# platform_smd2_map.net
KiCad netlist of a schematic drawn in EAGLE
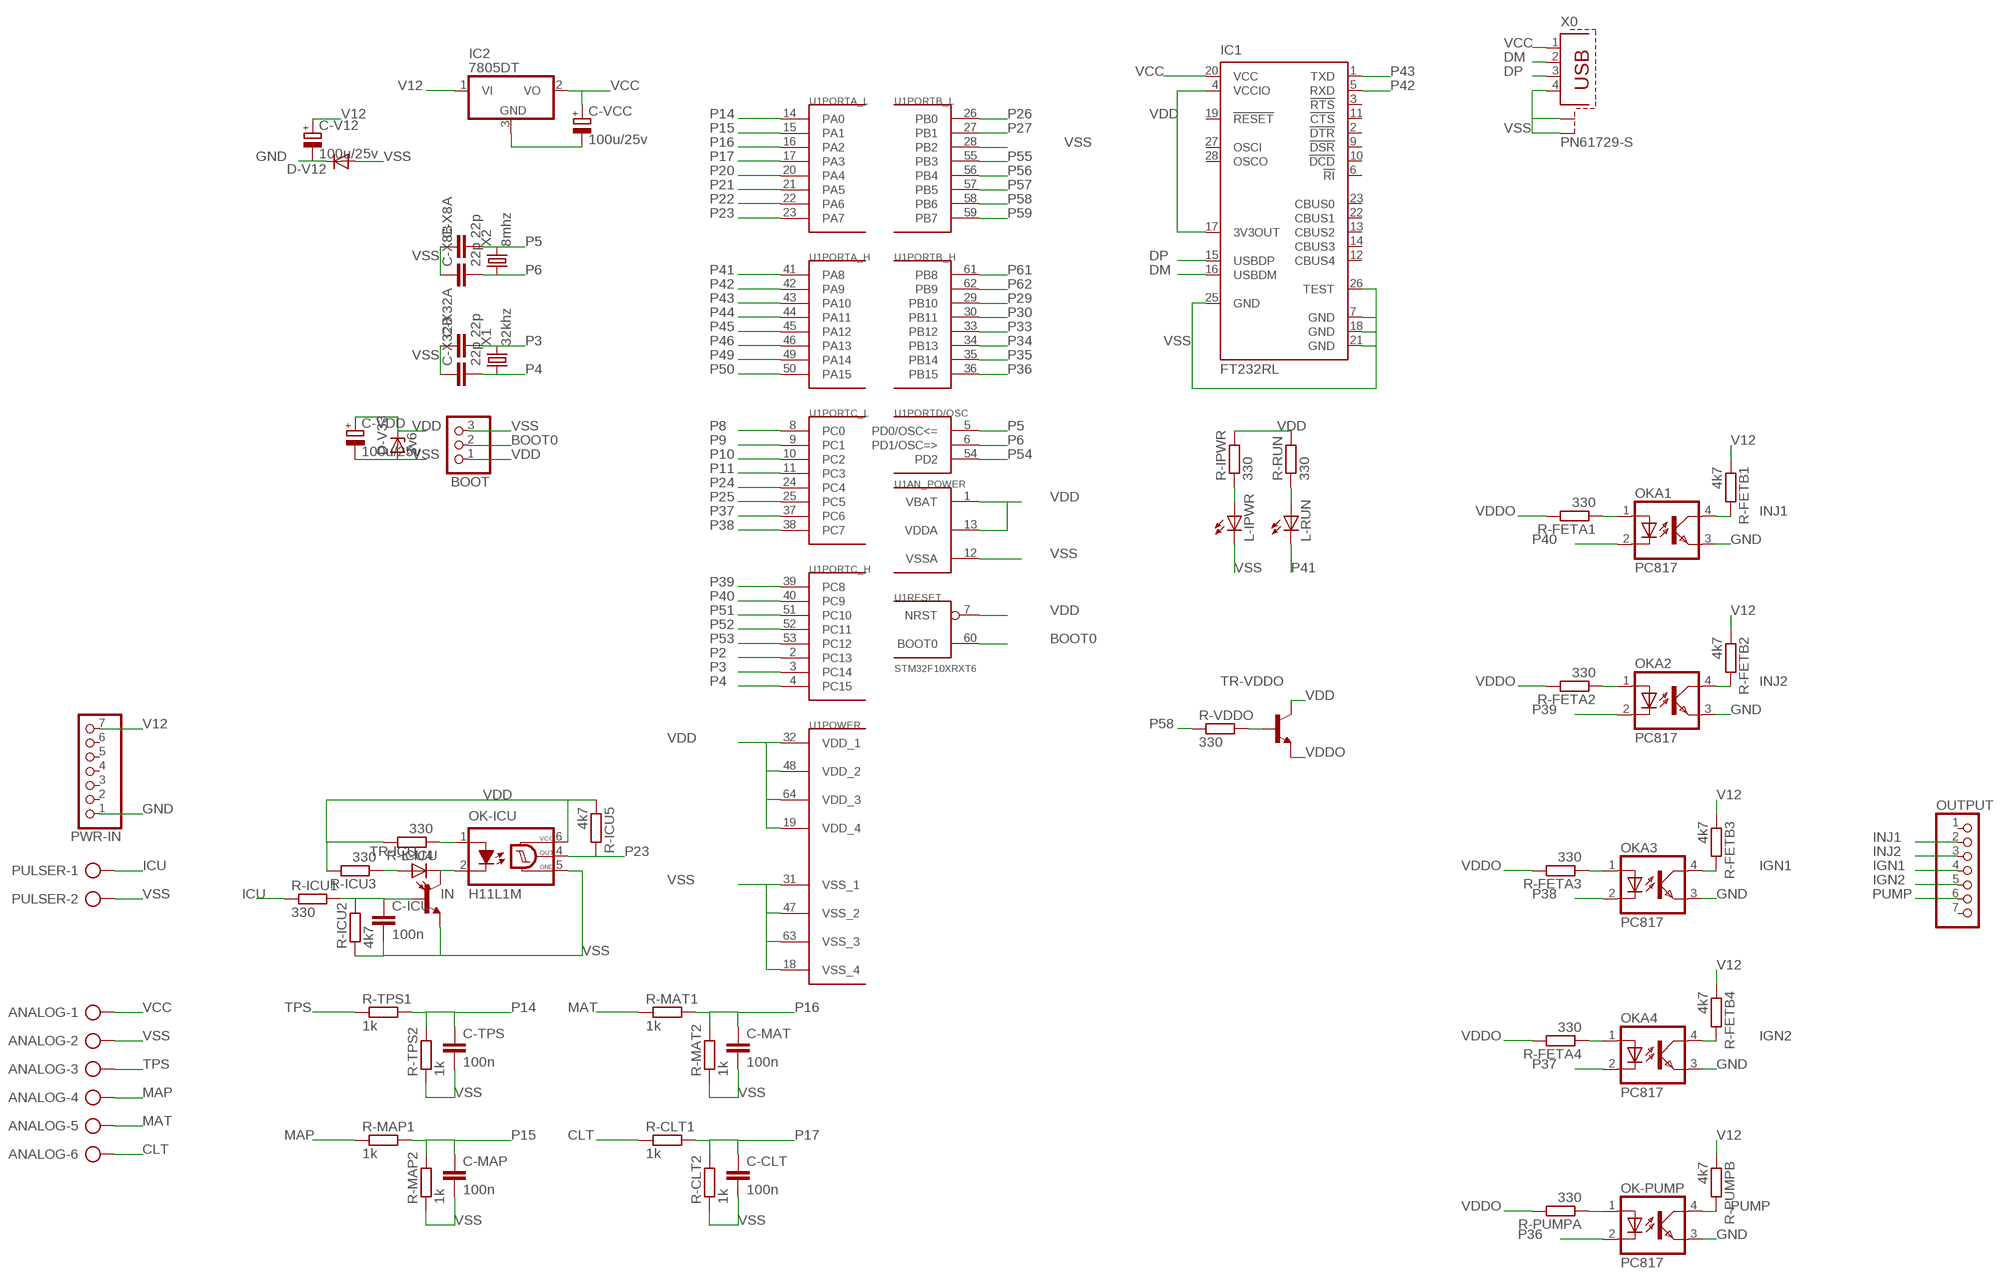
[diagram p0: schematic, sheet 1]

(export (version "E")
  (design (tool "Eeschema 10.0.6"))
  (components
    (comp (ref "ANALOG")
      (value "AK300/6")
      (footprint "eagle-import:AK300_6")
      (libsource (lib "eagle-import") (part "AK300/6"))
    )
    (comp (ref "BOOT")
      (value "PINHD-1X3")
      (footprint "eagle-import:1X03")
      (libsource (lib "eagle-import") (part "PINHD-1X3"))
    )
    (comp (ref "C-CLT")
      (value "100n")
      (footprint "eagle-import:C1206")
      (libsource (lib "eagle-import") (part "C-EUC1206"))
    )
    (comp (ref "C-ICU")
      (value "100n")
      (footprint "eagle-import:C1206")
      (libsource (lib "eagle-import") (part "C-EUC1206"))
    )
    (comp (ref "C-MAP")
      (value "100n")
      (footprint "eagle-import:C1206")
      (libsource (lib "eagle-import") (part "C-EUC1206"))
    )
    (comp (ref "C-MAT")
      (value "100n")
      (footprint "eagle-import:C1206")
      (libsource (lib "eagle-import") (part "C-EUC1206"))
    )
    (comp (ref "C-TPS")
      (value "100n")
      (footprint "eagle-import:C1206")
      (libsource (lib "eagle-import") (part "C-EUC1206"))
    )
    (comp (ref "C-V12")
      (value "100u/25v")
      (footprint "eagle-import:PANASONIC_D")
      (libsource (lib "eagle-import") (part "CPOL-EUD"))
    )
    (comp (ref "C-VCC")
      (value "100u/25v")
      (footprint "eagle-import:PANASONIC_D")
      (libsource (lib "eagle-import") (part "CPOL-EUD"))
    )
    (comp (ref "C-VDD")
      (value "100u/25v")
      (footprint "eagle-import:PANASONIC_D")
      (libsource (lib "eagle-import") (part "CPOL-EUD"))
    )
    (comp (ref "C-X8A")
      (value "22p")
      (footprint "eagle-import:C1206")
      (libsource (lib "eagle-import") (part "C-EUC1206"))
    )
    (comp (ref "C-X8B")
      (value "22p")
      (footprint "eagle-import:C1206")
      (libsource (lib "eagle-import") (part "C-EUC1206"))
    )
    (comp (ref "C-X32A")
      (value "22p")
      (footprint "eagle-import:C1206")
      (libsource (lib "eagle-import") (part "C-EUC1206"))
    )
    (comp (ref "C-X32B")
      (value "22p")
      (footprint "eagle-import:C1206")
      (libsource (lib "eagle-import") (part "C-EUC1206"))
    )
    (comp (ref "D-V12")
      (value "DIODE-SMB")
      (footprint "eagle-import:SMB")
      (libsource (lib "eagle-import") (part "DIODE-SMB"))
    )
    (comp (ref "D-V33")
      (value "3v6")
      (footprint "eagle-import:SMB")
      (libsource (lib "eagle-import") (part "ZENER-DIODESMB"))
    )
    (comp (ref "IC1")
      (value "FT232RL")
      (footprint "eagle-import:SSOP28")
      (libsource (lib "eagle-import") (part "FT232RL"))
    )
    (comp (ref "IC2")
      (value "7805DT")
      (footprint "eagle-import:TO252")
      (libsource (lib "eagle-import") (part "78DT05"))
    )
    (comp (ref "L-ICU")
      (value "LEDSML0805")
      (footprint "eagle-import:SML0805")
      (libsource (lib "eagle-import") (part "LEDSML0805"))
    )
    (comp (ref "L-IPWR")
      (value "LEDSMT1206")
      (footprint "eagle-import:1206")
      (libsource (lib "eagle-import") (part "LEDSMT1206"))
    )
    (comp (ref "L-RUN")
      (value "LEDSMT1206")
      (footprint "eagle-import:1206")
      (libsource (lib "eagle-import") (part "LEDSMT1206"))
    )
    (comp (ref "OK-ICU")
      (value "H11L1M")
      (footprint "eagle-import:DIL06")
      (fields (field (name "MF") "FAIRCHILD SEMICONDUCTOR") (field (name "MPN") "H11L1-M"))
      (libsource (lib "eagle-import") (part "H11LM1"))
    )
    (comp (ref "OK-PUMP")
      (value "PC817")
      (footprint "eagle-import:DIL04")
      (fields (field (name "MPN") "PC817X4J000F"))
      (libsource (lib "eagle-import") (part "PC817"))
    )
    (comp (ref "OKA1")
      (value "PC817")
      (footprint "eagle-import:DIL04")
      (fields (field (name "MPN") "PC817X4J000F"))
      (libsource (lib "eagle-import") (part "PC817"))
    )
    (comp (ref "OKA2")
      (value "PC817")
      (footprint "eagle-import:DIL04")
      (fields (field (name "MPN") "PC817X4J000F"))
      (libsource (lib "eagle-import") (part "PC817"))
    )
    (comp (ref "OKA3")
      (value "PC817")
      (footprint "eagle-import:DIL04")
      (fields (field (name "MPN") "PC817X4J000F"))
      (libsource (lib "eagle-import") (part "PC817"))
    )
    (comp (ref "OKA4")
      (value "PC817")
      (footprint "eagle-import:DIL04")
      (fields (field (name "MPN") "PC817X4J000F"))
      (libsource (lib "eagle-import") (part "PC817"))
    )
    (comp (ref "OUTPUT")
      (value "PINHD-1X7")
      (footprint "eagle-import:1X07")
      (libsource (lib "eagle-import") (part "PINHD-1X7"))
    )
    (comp (ref "PULSER")
      (value "AK300/2")
      (footprint "eagle-import:AK300_2")
      (libsource (lib "eagle-import") (part "AK300/2"))
    )
    (comp (ref "PWR-IN")
      (value "PINHD-1X7")
      (footprint "eagle-import:1X07")
      (libsource (lib "eagle-import") (part "PINHD-1X7"))
    )
    (comp (ref "R-CLT1")
      (value "1k")
      (footprint "eagle-import:R1206")
      (libsource (lib "eagle-import") (part "R-EU_R1206"))
    )
    (comp (ref "R-CLT2")
      (value "1k")
      (footprint "eagle-import:R1206")
      (libsource (lib "eagle-import") (part "R-EU_R1206"))
    )
    (comp (ref "R-FETA1")
      (value "330")
      (footprint "eagle-import:R1206")
      (libsource (lib "eagle-import") (part "R-EU_R1206"))
    )
    (comp (ref "R-FETA2")
      (value "330")
      (footprint "eagle-import:R1206")
      (libsource (lib "eagle-import") (part "R-EU_R1206"))
    )
    (comp (ref "R-FETA3")
      (value "330")
      (footprint "eagle-import:R1206")
      (libsource (lib "eagle-import") (part "R-EU_R1206"))
    )
    (comp (ref "R-FETA4")
      (value "330")
      (footprint "eagle-import:R1206")
      (libsource (lib "eagle-import") (part "R-EU_R1206"))
    )
    (comp (ref "R-FETB1")
      (value "4k7")
      (footprint "eagle-import:R1206")
      (libsource (lib "eagle-import") (part "R-EU_R1206"))
    )
    (comp (ref "R-FETB2")
      (value "4k7")
      (footprint "eagle-import:R1206")
      (libsource (lib "eagle-import") (part "R-EU_R1206"))
    )
    (comp (ref "R-FETB3")
      (value "4k7")
      (footprint "eagle-import:R1206")
      (libsource (lib "eagle-import") (part "R-EU_R1206"))
    )
    (comp (ref "R-FETB4")
      (value "4k7")
      (footprint "eagle-import:R1206")
      (libsource (lib "eagle-import") (part "R-EU_R1206"))
    )
    (comp (ref "R-ICU1")
      (value "330")
      (footprint "eagle-import:R1206")
      (libsource (lib "eagle-import") (part "R-EU_R1206"))
    )
    (comp (ref "R-ICU2")
      (value "4k7")
      (footprint "eagle-import:R1206")
      (libsource (lib "eagle-import") (part "R-EU_R1206"))
    )
    (comp (ref "R-ICU3")
      (value "330")
      (footprint "eagle-import:R1206")
      (libsource (lib "eagle-import") (part "R-EU_R1206"))
    )
    (comp (ref "R-ICU4")
      (value "330")
      (footprint "eagle-import:R1206")
      (libsource (lib "eagle-import") (part "R-EU_R1206"))
    )
    (comp (ref "R-ICU5")
      (value "4k7")
      (footprint "eagle-import:R1206")
      (libsource (lib "eagle-import") (part "R-EU_R1206"))
    )
    (comp (ref "R-IPWR")
      (value "330")
      (footprint "eagle-import:R1206")
      (libsource (lib "eagle-import") (part "R-EU_R1206"))
    )
    (comp (ref "R-MAP1")
      (value "1k")
      (footprint "eagle-import:R1206")
      (libsource (lib "eagle-import") (part "R-EU_R1206"))
    )
    (comp (ref "R-MAP2")
      (value "1k")
      (footprint "eagle-import:R1206")
      (libsource (lib "eagle-import") (part "R-EU_R1206"))
    )
    (comp (ref "R-MAT1")
      (value "1k")
      (footprint "eagle-import:R1206")
      (libsource (lib "eagle-import") (part "R-EU_R1206"))
    )
    (comp (ref "R-MAT2")
      (value "1k")
      (footprint "eagle-import:R1206")
      (libsource (lib "eagle-import") (part "R-EU_R1206"))
    )
    (comp (ref "R-PUMPA")
      (value "330")
      (footprint "eagle-import:R1206")
      (libsource (lib "eagle-import") (part "R-EU_R1206"))
    )
    (comp (ref "R-PUMPB")
      (value "4k7")
      (footprint "eagle-import:R1206")
      (libsource (lib "eagle-import") (part "R-EU_R1206"))
    )
    (comp (ref "R-RUN")
      (value "330")
      (footprint "eagle-import:R1206")
      (libsource (lib "eagle-import") (part "R-EU_R1206"))
    )
    (comp (ref "R-TPS1")
      (value "1k")
      (footprint "eagle-import:R1206")
      (libsource (lib "eagle-import") (part "R-EU_R1206"))
    )
    (comp (ref "R-TPS2")
      (value "1k")
      (footprint "eagle-import:R1206")
      (libsource (lib "eagle-import") (part "R-EU_R1206"))
    )
    (comp (ref "R-VDDO")
      (value "330")
      (footprint "eagle-import:R0805")
      (libsource (lib "eagle-import") (part "R-EU_R0805"))
    )
    (comp (ref "TR-ICU")
      (value "MMBT3904LT1-NPN-SOT23-BEC")
      (footprint "eagle-import:SOT23-BEC")
      (libsource (lib "eagle-import") (part "-NPN-SOT23-BECMMBT3904LT1"))
    )
    (comp (ref "TR-VDDO")
      (value "MMBT3904LT1-NPN-SOT23-BEC")
      (footprint "eagle-import:SOT23-BEC")
      (libsource (lib "eagle-import") (part "-NPN-SOT23-BECMMBT3904LT1"))
    )
    (comp (ref "U1")
      (value "STM32F10XRXT6")
      (footprint "eagle-import:TQFP64")
      (libsource (lib "eagle-import") (part "STM32F10XRXT6"))
    )
    (comp (ref "X0")
      (value "PN61729-S")
      (footprint "eagle-import:PN61729-S")
      (libsource (lib "eagle-import") (part "PN61729-S"))
    )
    (comp (ref "X1")
      (value "32khz")
      (footprint "eagle-import:TC26V")
      (libsource (lib "eagle-import") (part "CRYSTALTC26V"))
    )
    (comp (ref "X2")
      (value "8mhz")
      (footprint "eagle-import:HC49U-V")
      (libsource (lib "eagle-import") (part "CRYSTALHC49U-V"))
    )
  )
  (nets
    (net (code "1") (name "/BOOT0") (class "Default")
      (node (ref "BOOT") (pin "2") (pinfunction "2_2") (pintype "passive"))
      (node (ref "U1") (pin "60") (pinfunction "BOOT0_60") (pintype "input"))
    )
    (net (code "2") (name "/CLT") (class "Default")
      (node (ref "ANALOG") (pin "6") (pinfunction "KL_6") (pintype "passive"))
      (node (ref "R-CLT1") (pin "1") (pinfunction "1_1") (pintype "passive"))
    )
    (net (code "3") (name "/DM") (class "Default")
      (node (ref "IC1") (pin "16") (pinfunction "USBDM_16") (pintype "bidirectional"))
      (node (ref "X0") (pin "2") (pinfunction "2_2") (pintype "passive"))
    )
    (net (code "4") (name "/DP") (class "Default")
      (node (ref "IC1") (pin "15") (pinfunction "USBDP_15") (pintype "bidirectional"))
      (node (ref "X0") (pin "3") (pinfunction "3_3") (pintype "passive"))
    )
    (net (code "5") (name "/GND") (class "Default")
      (node (ref "C-V12") (pin "-") (pinfunction "-_-") (pintype "passive"))
      (node (ref "D-V12") (pin "C") (pinfunction "C_C") (pintype "passive"))
      (node (ref "OK-PUMP") (pin "3") (pinfunction "EMIT_3") (pintype "passive"))
      (node (ref "OKA1") (pin "3") (pinfunction "EMIT_3") (pintype "passive"))
      (node (ref "OKA2") (pin "3") (pinfunction "EMIT_3") (pintype "passive"))
      (node (ref "OKA3") (pin "3") (pinfunction "EMIT_3") (pintype "passive"))
      (node (ref "OKA4") (pin "3") (pinfunction "EMIT_3") (pintype "passive"))
      (node (ref "PWR-IN") (pin "1") (pinfunction "1_1") (pintype "passive"))
    )
    (net (code "6") (name "/ICU") (class "Default")
      (node (ref "PULSER") (pin "1") (pinfunction "KL_1") (pintype "passive"))
      (node (ref "R-ICU1") (pin "1") (pinfunction "1_1") (pintype "passive"))
    )
    (net (code "7") (name "/IGN1") (class "Default")
      (node (ref "OKA3") (pin "4") (pinfunction "COL_4") (pintype "passive"))
      (node (ref "OUTPUT") (pin "4") (pinfunction "4_4") (pintype "passive"))
      (node (ref "R-FETB3") (pin "2") (pinfunction "2_2") (pintype "passive"))
    )
    (net (code "8") (name "/IGN2") (class "Default")
      (node (ref "OKA4") (pin "4") (pinfunction "COL_4") (pintype "passive"))
      (node (ref "OUTPUT") (pin "5") (pinfunction "5_5") (pintype "passive"))
      (node (ref "R-FETB4") (pin "2") (pinfunction "2_2") (pintype "passive"))
    )
    (net (code "9") (name "/IN") (class "Default")
      (node (ref "L-ICU") (pin "C") (pinfunction "C_C") (pintype "passive"))
      (node (ref "OK-ICU") (pin "2") (pinfunction "C_2") (pintype "passive"))
      (node (ref "TR-ICU") (pin "C") (pinfunction "C_C") (pintype "passive"))
    )
    (net (code "10") (name "/INJ1") (class "Default")
      (node (ref "OKA1") (pin "4") (pinfunction "COL_4") (pintype "passive"))
      (node (ref "OUTPUT") (pin "2") (pinfunction "2_2") (pintype "passive"))
      (node (ref "R-FETB1") (pin "2") (pinfunction "2_2") (pintype "passive"))
    )
    (net (code "11") (name "/INJ2") (class "Default")
      (node (ref "OKA2") (pin "4") (pinfunction "COL_4") (pintype "passive"))
      (node (ref "OUTPUT") (pin "3") (pinfunction "3_3") (pintype "passive"))
      (node (ref "R-FETB2") (pin "2") (pinfunction "2_2") (pintype "passive"))
    )
    (net (code "12") (name "/MAP") (class "Default")
      (node (ref "ANALOG") (pin "4") (pinfunction "KL_4") (pintype "passive"))
      (node (ref "R-MAP1") (pin "1") (pinfunction "1_1") (pintype "passive"))
    )
    (net (code "13") (name "/MAT") (class "Default")
      (node (ref "ANALOG") (pin "5") (pinfunction "KL_5") (pintype "passive"))
      (node (ref "R-MAT1") (pin "1") (pinfunction "1_1") (pintype "passive"))
    )
    (net (code "14") (name "/P2") (class "Default")
      (node (ref "U1") (pin "2") (pinfunction "PC13_2") (pintype "bidirectional"))
    )
    (net (code "15") (name "/P3") (class "Default")
      (node (ref "C-X32A") (pin "2") (pinfunction "2_2") (pintype "passive"))
      (node (ref "U1") (pin "3") (pinfunction "PC14_3") (pintype "bidirectional"))
      (node (ref "X1") (pin "2") (pinfunction "2_2") (pintype "passive"))
    )
    (net (code "16") (name "/P4") (class "Default")
      (node (ref "C-X32B") (pin "2") (pinfunction "2_2") (pintype "passive"))
      (node (ref "U1") (pin "4") (pinfunction "PC15_4") (pintype "bidirectional"))
      (node (ref "X1") (pin "1") (pinfunction "1_1") (pintype "passive"))
    )
    (net (code "17") (name "/P5") (class "Default")
      (node (ref "C-X8A") (pin "2") (pinfunction "2_2") (pintype "passive"))
      (node (ref "U1") (pin "5") (pinfunction "PD0/OSC<=_5") (pintype "bidirectional"))
      (node (ref "X2") (pin "2") (pinfunction "2_2") (pintype "passive"))
    )
    (net (code "18") (name "/P6") (class "Default")
      (node (ref "C-X8B") (pin "2") (pinfunction "2_2") (pintype "passive"))
      (node (ref "U1") (pin "6") (pinfunction "PD1/OSC=>_6") (pintype "bidirectional"))
      (node (ref "X2") (pin "1") (pinfunction "1_1") (pintype "passive"))
    )
    (net (code "19") (name "/P8") (class "Default")
      (node (ref "U1") (pin "8") (pinfunction "PC0_8") (pintype "bidirectional"))
    )
    (net (code "20") (name "/P9") (class "Default")
      (node (ref "U1") (pin "9") (pinfunction "PC1_9") (pintype "bidirectional"))
    )
    (net (code "21") (name "/P10") (class "Default")
      (node (ref "U1") (pin "10") (pinfunction "PC2_10") (pintype "bidirectional"))
    )
    (net (code "22") (name "/P11") (class "Default")
      (node (ref "U1") (pin "11") (pinfunction "PC3_11") (pintype "bidirectional"))
    )
    (net (code "23") (name "/P14") (class "Default")
      (node (ref "C-TPS") (pin "1") (pinfunction "1_1") (pintype "passive"))
      (node (ref "R-TPS1") (pin "2") (pinfunction "2_2") (pintype "passive"))
      (node (ref "R-TPS2") (pin "2") (pinfunction "2_2") (pintype "passive"))
      (node (ref "U1") (pin "14") (pinfunction "PA0_14") (pintype "bidirectional"))
    )
    (net (code "24") (name "/P15") (class "Default")
      (node (ref "C-MAP") (pin "1") (pinfunction "1_1") (pintype "passive"))
      (node (ref "R-MAP1") (pin "2") (pinfunction "2_2") (pintype "passive"))
      (node (ref "R-MAP2") (pin "2") (pinfunction "2_2") (pintype "passive"))
      (node (ref "U1") (pin "15") (pinfunction "PA1_15") (pintype "bidirectional"))
    )
    (net (code "25") (name "/P16") (class "Default")
      (node (ref "C-MAT") (pin "1") (pinfunction "1_1") (pintype "passive"))
      (node (ref "R-MAT1") (pin "2") (pinfunction "2_2") (pintype "passive"))
      (node (ref "R-MAT2") (pin "2") (pinfunction "2_2") (pintype "passive"))
      (node (ref "U1") (pin "16") (pinfunction "PA2_16") (pintype "bidirectional"))
    )
    (net (code "26") (name "/P17") (class "Default")
      (node (ref "C-CLT") (pin "1") (pinfunction "1_1") (pintype "passive"))
      (node (ref "R-CLT1") (pin "2") (pinfunction "2_2") (pintype "passive"))
      (node (ref "R-CLT2") (pin "2") (pinfunction "2_2") (pintype "passive"))
      (node (ref "U1") (pin "17") (pinfunction "PA3_17") (pintype "bidirectional"))
    )
    (net (code "27") (name "/P20") (class "Default")
      (node (ref "U1") (pin "20") (pinfunction "PA4_20") (pintype "bidirectional"))
    )
    (net (code "28") (name "/P21") (class "Default")
      (node (ref "U1") (pin "21") (pinfunction "PA5_21") (pintype "bidirectional"))
    )
    (net (code "29") (name "/P22") (class "Default")
      (node (ref "U1") (pin "22") (pinfunction "PA6_22") (pintype "bidirectional"))
    )
    (net (code "30") (name "/P23") (class "Default")
      (node (ref "OK-ICU") (pin "4") (pinfunction "OUT_4") (pintype "output"))
      (node (ref "R-ICU5") (pin "2") (pinfunction "2_2") (pintype "passive"))
      (node (ref "U1") (pin "23") (pinfunction "PA7_23") (pintype "bidirectional"))
    )
    (net (code "31") (name "/P24") (class "Default")
      (node (ref "U1") (pin "24") (pinfunction "PC4_24") (pintype "bidirectional"))
    )
    (net (code "32") (name "/P25") (class "Default")
      (node (ref "U1") (pin "25") (pinfunction "PC5_25") (pintype "bidirectional"))
    )
    (net (code "33") (name "/P26") (class "Default")
      (node (ref "U1") (pin "26") (pinfunction "PB0_26") (pintype "bidirectional"))
    )
    (net (code "34") (name "/P27") (class "Default")
      (node (ref "U1") (pin "27") (pinfunction "PB1_27") (pintype "bidirectional"))
    )
    (net (code "35") (name "/P29") (class "Default")
      (node (ref "U1") (pin "29") (pinfunction "PB10_29") (pintype "bidirectional"))
    )
    (net (code "36") (name "/P30") (class "Default")
      (node (ref "U1") (pin "30") (pinfunction "PB11_30") (pintype "bidirectional"))
    )
    (net (code "37") (name "/P33") (class "Default")
      (node (ref "U1") (pin "33") (pinfunction "PB12_33") (pintype "bidirectional"))
    )
    (net (code "38") (name "/P34") (class "Default")
      (node (ref "U1") (pin "34") (pinfunction "PB13_34") (pintype "bidirectional"))
    )
    (net (code "39") (name "/P35") (class "Default")
      (node (ref "U1") (pin "35") (pinfunction "PB14_35") (pintype "bidirectional"))
    )
    (net (code "40") (name "/P36") (class "Default")
      (node (ref "OK-PUMP") (pin "2") (pinfunction "C_2") (pintype "passive"))
      (node (ref "U1") (pin "36") (pinfunction "PB15_36") (pintype "bidirectional"))
    )
    (net (code "41") (name "/P37") (class "Default")
      (node (ref "OKA4") (pin "2") (pinfunction "C_2") (pintype "passive"))
      (node (ref "U1") (pin "37") (pinfunction "PC6_37") (pintype "bidirectional"))
    )
    (net (code "42") (name "/P38") (class "Default")
      (node (ref "OKA3") (pin "2") (pinfunction "C_2") (pintype "passive"))
      (node (ref "U1") (pin "38") (pinfunction "PC7_38") (pintype "bidirectional"))
    )
    (net (code "43") (name "/P39") (class "Default")
      (node (ref "OKA2") (pin "2") (pinfunction "C_2") (pintype "passive"))
      (node (ref "U1") (pin "39") (pinfunction "PC8_39") (pintype "bidirectional"))
    )
    (net (code "44") (name "/P40") (class "Default")
      (node (ref "OKA1") (pin "2") (pinfunction "C_2") (pintype "passive"))
      (node (ref "U1") (pin "40") (pinfunction "PC9_40") (pintype "bidirectional"))
    )
    (net (code "45") (name "/P41") (class "Default")
      (node (ref "L-RUN") (pin "C") (pinfunction "C_C") (pintype "passive"))
      (node (ref "U1") (pin "41") (pinfunction "PA8_41") (pintype "bidirectional"))
    )
    (net (code "46") (name "/P42") (class "Default")
      (node (ref "IC1") (pin "5") (pinfunction "RXD_5") (pintype "input"))
      (node (ref "U1") (pin "42") (pinfunction "PA9_42") (pintype "bidirectional"))
    )
    (net (code "47") (name "/P43") (class "Default")
      (node (ref "IC1") (pin "1") (pinfunction "TXD_1") (pintype "output"))
      (node (ref "U1") (pin "43") (pinfunction "PA10_43") (pintype "bidirectional"))
    )
    (net (code "48") (name "/P44") (class "Default")
      (node (ref "U1") (pin "44") (pinfunction "PA11_44") (pintype "bidirectional"))
    )
    (net (code "49") (name "/P45") (class "Default")
      (node (ref "U1") (pin "45") (pinfunction "PA12_45") (pintype "bidirectional"))
    )
    (net (code "50") (name "/P46") (class "Default")
      (node (ref "U1") (pin "46") (pinfunction "PA13_46") (pintype "bidirectional"))
    )
    (net (code "51") (name "/P49") (class "Default")
      (node (ref "U1") (pin "49") (pinfunction "PA14_49") (pintype "bidirectional"))
    )
    (net (code "52") (name "/P50") (class "Default")
      (node (ref "U1") (pin "50") (pinfunction "PA15_50") (pintype "bidirectional"))
    )
    (net (code "53") (name "/P51") (class "Default")
      (node (ref "U1") (pin "51") (pinfunction "PC10_51") (pintype "bidirectional"))
    )
    (net (code "54") (name "/P52") (class "Default")
      (node (ref "U1") (pin "52") (pinfunction "PC11_52") (pintype "bidirectional"))
    )
    (net (code "55") (name "/P53") (class "Default")
      (node (ref "U1") (pin "53") (pinfunction "PC12_53") (pintype "bidirectional"))
    )
    (net (code "56") (name "/P54") (class "Default")
      (node (ref "U1") (pin "54") (pinfunction "PD2_54") (pintype "bidirectional"))
    )
    (net (code "57") (name "/P55") (class "Default")
      (node (ref "U1") (pin "55") (pinfunction "PB3_55") (pintype "bidirectional"))
    )
    (net (code "58") (name "/P56") (class "Default")
      (node (ref "U1") (pin "56") (pinfunction "PB4_56") (pintype "bidirectional"))
    )
    (net (code "59") (name "/P57") (class "Default")
      (node (ref "U1") (pin "57") (pinfunction "PB5_57") (pintype "bidirectional"))
    )
    (net (code "60") (name "/P58") (class "Default")
      (node (ref "R-VDDO") (pin "1") (pinfunction "1_1") (pintype "passive"))
      (node (ref "U1") (pin "58") (pinfunction "PB6_58") (pintype "bidirectional"))
    )
    (net (code "61") (name "/P59") (class "Default")
      (node (ref "U1") (pin "59") (pinfunction "PB7_59") (pintype "bidirectional"))
    )
    (net (code "62") (name "/P61") (class "Default")
      (node (ref "U1") (pin "61") (pinfunction "PB8_61") (pintype "bidirectional"))
    )
    (net (code "63") (name "/P62") (class "Default")
      (node (ref "U1") (pin "62") (pinfunction "PB9_62") (pintype "bidirectional"))
    )
    (net (code "64") (name "/PUMP") (class "Default")
      (node (ref "OK-PUMP") (pin "4") (pinfunction "COL_4") (pintype "passive"))
      (node (ref "OUTPUT") (pin "6") (pinfunction "6_6") (pintype "passive"))
      (node (ref "R-PUMPB") (pin "2") (pinfunction "2_2") (pintype "passive"))
    )
    (net (code "65") (name "/TPS") (class "Default")
      (node (ref "ANALOG") (pin "3") (pinfunction "KL_3") (pintype "passive"))
      (node (ref "R-TPS1") (pin "1") (pinfunction "1_1") (pintype "passive"))
    )
    (net (code "66") (name "/V12") (class "Default")
      (node (ref "C-V12") (pin "+") (pinfunction "+_+") (pintype "passive"))
      (node (ref "IC2") (pin "1") (pinfunction "VI_1") (pintype "input"))
      (node (ref "PWR-IN") (pin "7") (pinfunction "7_7") (pintype "passive"))
      (node (ref "R-FETB1") (pin "1") (pinfunction "1_1") (pintype "passive"))
      (node (ref "R-FETB2") (pin "1") (pinfunction "1_1") (pintype "passive"))
      (node (ref "R-FETB3") (pin "1") (pinfunction "1_1") (pintype "passive"))
      (node (ref "R-FETB4") (pin "1") (pinfunction "1_1") (pintype "passive"))
      (node (ref "R-PUMPB") (pin "1") (pinfunction "1_1") (pintype "passive"))
    )
    (net (code "67") (name "/VCC") (class "Default")
      (node (ref "ANALOG") (pin "1") (pinfunction "KL_1") (pintype "passive"))
      (node (ref "C-VCC") (pin "+") (pinfunction "+_+") (pintype "passive"))
      (node (ref "IC1") (pin "20") (pinfunction "VCC_20") (pintype "power_in"))
      (node (ref "IC2") (pin "2") (pinfunction "VO_2") (pintype "passive"))
      (node (ref "X0") (pin "1") (pinfunction "1_1") (pintype "passive"))
    )
    (net (code "68") (name "/VDD") (class "Default")
      (node (ref "BOOT") (pin "1") (pinfunction "1_1") (pintype "passive"))
      (node (ref "C-VDD") (pin "+") (pinfunction "+_+") (pintype "passive"))
      (node (ref "D-V33") (pin "C") (pinfunction "C_C") (pintype "passive"))
      (node (ref "IC1") (pin "17") (pinfunction "3V3OUT_17") (pintype "output"))
      (node (ref "IC1") (pin "4") (pinfunction "VCCIO_4") (pintype "power_in"))
      (node (ref "OK-ICU") (pin "6") (pinfunction "VCC_6") (pintype "power_in"))
      (node (ref "R-ICU3") (pin "2") (pinfunction "2_2") (pintype "passive"))
      (node (ref "R-ICU4") (pin "2") (pinfunction "2_2") (pintype "passive"))
      (node (ref "R-ICU5") (pin "1") (pinfunction "1_1") (pintype "passive"))
      (node (ref "R-IPWR") (pin "2") (pinfunction "2_2") (pintype "passive"))
      (node (ref "R-RUN") (pin "2") (pinfunction "2_2") (pintype "passive"))
      (node (ref "TR-VDDO") (pin "C") (pinfunction "C_C") (pintype "passive"))
      (node (ref "U1") (pin "1") (pinfunction "VBAT_1") (pintype "power_in"))
      (node (ref "U1") (pin "13") (pinfunction "VDDA_13") (pintype "power_in"))
      (node (ref "U1") (pin "19") (pinfunction "VDD_4_19") (pintype "power_in"))
      (node (ref "U1") (pin "32") (pinfunction "VDD_1_32") (pintype "power_in"))
      (node (ref "U1") (pin "48") (pinfunction "VDD_2_48") (pintype "power_in"))
      (node (ref "U1") (pin "64") (pinfunction "VDD_3_64") (pintype "power_in"))
      (node (ref "U1") (pin "7") (pinfunction "NRST_7") (pintype "input"))
    )
    (net (code "69") (name "/VDDO") (class "Default")
      (node (ref "R-FETA1") (pin "2") (pinfunction "2_2") (pintype "passive"))
      (node (ref "R-FETA2") (pin "2") (pinfunction "2_2") (pintype "passive"))
      (node (ref "R-FETA3") (pin "2") (pinfunction "2_2") (pintype "passive"))
      (node (ref "R-FETA4") (pin "2") (pinfunction "2_2") (pintype "passive"))
      (node (ref "R-PUMPA") (pin "2") (pinfunction "2_2") (pintype "passive"))
      (node (ref "TR-VDDO") (pin "E") (pinfunction "E_E") (pintype "passive"))
    )
    (net (code "70") (name "/VSS") (class "Default")
      (node (ref "ANALOG") (pin "2") (pinfunction "KL_2") (pintype "passive"))
      (node (ref "BOOT") (pin "3") (pinfunction "3_3") (pintype "passive"))
      (node (ref "C-CLT") (pin "2") (pinfunction "2_2") (pintype "passive"))
      (node (ref "C-ICU") (pin "2") (pinfunction "2_2") (pintype "passive"))
      (node (ref "C-MAP") (pin "2") (pinfunction "2_2") (pintype "passive"))
      (node (ref "C-MAT") (pin "2") (pinfunction "2_2") (pintype "passive"))
      (node (ref "C-TPS") (pin "2") (pinfunction "2_2") (pintype "passive"))
      (node (ref "C-VCC") (pin "-") (pinfunction "-_-") (pintype "passive"))
      (node (ref "C-VDD") (pin "-") (pinfunction "-_-") (pintype "passive"))
      (node (ref "C-X32A") (pin "1") (pinfunction "1_1") (pintype "passive"))
      (node (ref "C-X32B") (pin "1") (pinfunction "1_1") (pintype "passive"))
      (node (ref "C-X8A") (pin "1") (pinfunction "1_1") (pintype "passive"))
      (node (ref "C-X8B") (pin "1") (pinfunction "1_1") (pintype "passive"))
      (node (ref "D-V12") (pin "A") (pinfunction "A_A") (pintype "passive"))
      (node (ref "D-V33") (pin "A") (pinfunction "A_A") (pintype "passive"))
      (node (ref "IC1") (pin "18") (pinfunction "GND_18") (pintype "power_in"))
      (node (ref "IC1") (pin "21") (pinfunction "GND_21") (pintype "power_in"))
      (node (ref "IC1") (pin "25") (pinfunction "GND_25") (pintype "power_in"))
      (node (ref "IC1") (pin "26") (pinfunction "TEST_26") (pintype "input"))
      (node (ref "IC1") (pin "7") (pinfunction "GND_7") (pintype "power_in"))
      (node (ref "IC2") (pin "3") (pinfunction "GND_3") (pintype "passive"))
      (node (ref "L-IPWR") (pin "C") (pinfunction "C_C") (pintype "passive"))
      (node (ref "OK-ICU") (pin "5") (pinfunction "GND_5") (pintype "power_in"))
      (node (ref "PULSER") (pin "2") (pinfunction "KL_2") (pintype "passive"))
      (node (ref "R-CLT2") (pin "1") (pinfunction "1_1") (pintype "passive"))
      (node (ref "R-ICU2") (pin "1") (pinfunction "1_1") (pintype "passive"))
      (node (ref "R-MAP2") (pin "1") (pinfunction "1_1") (pintype "passive"))
      (node (ref "R-MAT2") (pin "1") (pinfunction "1_1") (pintype "passive"))
      (node (ref "R-TPS2") (pin "1") (pinfunction "1_1") (pintype "passive"))
      (node (ref "TR-ICU") (pin "E") (pinfunction "E_E") (pintype "passive"))
      (node (ref "U1") (pin "12") (pinfunction "VSSA_12") (pintype "power_in"))
      (node (ref "U1") (pin "18") (pinfunction "VSS_4_18") (pintype "power_in"))
      (node (ref "U1") (pin "28") (pinfunction "PB2_28") (pintype "bidirectional"))
      (node (ref "U1") (pin "31") (pinfunction "VSS_1_31") (pintype "power_in"))
      (node (ref "U1") (pin "47") (pinfunction "VSS_2_47") (pintype "power_in"))
      (node (ref "U1") (pin "63") (pinfunction "VSS_3_63") (pintype "power_in"))
      (node (ref "X0") (pin "4") (pinfunction "4_4") (pintype "passive"))
      (node (ref "X0") (pin "S1") (pinfunction "S1_S1") (pintype "passive"))
      (node (ref "X0") (pin "S2") (pinfunction "S2_S2") (pintype "passive"))
    )
    (net (code "71") (name "Net-(C-ICU-Pad1)") (class "Default")
      (node (ref "C-ICU") (pin "1") (pinfunction "1_1") (pintype "passive"))
      (node (ref "R-ICU1") (pin "2") (pinfunction "2_2") (pintype "passive"))
      (node (ref "R-ICU2") (pin "2") (pinfunction "2_2") (pintype "passive"))
      (node (ref "TR-ICU") (pin "B") (pinfunction "B_B") (pintype "passive"))
    )
    (net (code "72") (name "Net-(L-ICU-PadA)") (class "Default")
      (node (ref "L-ICU") (pin "A") (pinfunction "A_A") (pintype "passive"))
      (node (ref "R-ICU3") (pin "1") (pinfunction "1_1") (pintype "passive"))
    )
    (net (code "73") (name "Net-(L-IPWR-PadA)") (class "Default")
      (node (ref "L-IPWR") (pin "A") (pinfunction "A_A") (pintype "passive"))
      (node (ref "R-IPWR") (pin "1") (pinfunction "1_1") (pintype "passive"))
    )
    (net (code "74") (name "Net-(L-RUN-PadA)") (class "Default")
      (node (ref "L-RUN") (pin "A") (pinfunction "A_A") (pintype "passive"))
      (node (ref "R-RUN") (pin "1") (pinfunction "1_1") (pintype "passive"))
    )
    (net (code "75") (name "Net-(OK-ICU-A)") (class "Default")
      (node (ref "OK-ICU") (pin "1") (pinfunction "A_1") (pintype "passive"))
      (node (ref "R-ICU4") (pin "1") (pinfunction "1_1") (pintype "passive"))
    )
    (net (code "76") (name "Net-(OK-PUMP-A)") (class "Default")
      (node (ref "OK-PUMP") (pin "1") (pinfunction "A_1") (pintype "passive"))
      (node (ref "R-PUMPA") (pin "1") (pinfunction "1_1") (pintype "passive"))
    )
    (net (code "77") (name "Net-(OKA1-A)") (class "Default")
      (node (ref "OKA1") (pin "1") (pinfunction "A_1") (pintype "passive"))
      (node (ref "R-FETA1") (pin "1") (pinfunction "1_1") (pintype "passive"))
    )
    (net (code "78") (name "Net-(OKA2-A)") (class "Default")
      (node (ref "OKA2") (pin "1") (pinfunction "A_1") (pintype "passive"))
      (node (ref "R-FETA2") (pin "1") (pinfunction "1_1") (pintype "passive"))
    )
    (net (code "79") (name "Net-(OKA3-A)") (class "Default")
      (node (ref "OKA3") (pin "1") (pinfunction "A_1") (pintype "passive"))
      (node (ref "R-FETA3") (pin "1") (pinfunction "1_1") (pintype "passive"))
    )
    (net (code "80") (name "Net-(OKA4-A)") (class "Default")
      (node (ref "OKA4") (pin "1") (pinfunction "A_1") (pintype "passive"))
      (node (ref "R-FETA4") (pin "1") (pinfunction "1_1") (pintype "passive"))
    )
    (net (code "81") (name "Net-(R-VDDO-Pad2)") (class "Default")
      (node (ref "R-VDDO") (pin "2") (pinfunction "2_2") (pintype "passive"))
      (node (ref "TR-VDDO") (pin "B") (pinfunction "B_B") (pintype "passive"))
    )
    (net (code "82") (name "unconnected-(IC1-CBUS0-Pad23)") (class "Default")
      (node (ref "IC1") (pin "23") (pinfunction "CBUS0_23") (pintype "bidirectional"))
    )
    (net (code "83") (name "unconnected-(IC1-CBUS1-Pad22)") (class "Default")
      (node (ref "IC1") (pin "22") (pinfunction "CBUS1_22") (pintype "bidirectional"))
    )
    (net (code "84") (name "unconnected-(IC1-CBUS2-Pad13)") (class "Default")
      (node (ref "IC1") (pin "13") (pinfunction "CBUS2_13") (pintype "bidirectional"))
    )
    (net (code "85") (name "unconnected-(IC1-CBUS3-Pad14)") (class "Default")
      (node (ref "IC1") (pin "14") (pinfunction "CBUS3_14") (pintype "bidirectional"))
    )
    (net (code "86") (name "unconnected-(IC1-CBUS4-Pad12)") (class "Default")
      (node (ref "IC1") (pin "12") (pinfunction "CBUS4_12") (pintype "bidirectional"))
    )
    (net (code "87") (name "unconnected-(IC1-OSCI-Pad27)") (class "Default")
      (node (ref "IC1") (pin "27") (pinfunction "OSCI_27") (pintype "input"))
    )
    (net (code "88") (name "unconnected-(IC1-OSCO-Pad28)") (class "Default")
      (node (ref "IC1") (pin "28") (pinfunction "OSCO_28") (pintype "output"))
    )
    (net (code "89") (name "unconnected-(IC1-~{CTS}-Pad11)") (class "Default")
      (node (ref "IC1") (pin "11") (pinfunction "~{CTS}_11") (pintype "input"))
    )
    (net (code "90") (name "unconnected-(IC1-~{DCD}-Pad10)") (class "Default")
      (node (ref "IC1") (pin "10") (pinfunction "~{DCD}_10") (pintype "input"))
    )
    (net (code "91") (name "unconnected-(IC1-~{DSR}-Pad9)") (class "Default")
      (node (ref "IC1") (pin "9") (pinfunction "~{DSR}_9") (pintype "input"))
    )
    (net (code "92") (name "unconnected-(IC1-~{DTR}-Pad2)") (class "Default")
      (node (ref "IC1") (pin "2") (pinfunction "~{DTR}_2") (pintype "output"))
    )
    (net (code "93") (name "unconnected-(IC1-~{RESET}-Pad19)") (class "Default")
      (node (ref "IC1") (pin "19") (pinfunction "~{RESET}_19") (pintype "input"))
    )
    (net (code "94") (name "unconnected-(IC1-~{RI}-Pad6)") (class "Default")
      (node (ref "IC1") (pin "6") (pinfunction "~{RI}_6") (pintype "input"))
    )
    (net (code "95") (name "unconnected-(IC1-~{RTS}-Pad3)") (class "Default")
      (node (ref "IC1") (pin "3") (pinfunction "~{RTS}_3") (pintype "output"))
    )
    (net (code "96") (name "unconnected-(OUTPUT-Pad1)") (class "Default")
      (node (ref "OUTPUT") (pin "1") (pinfunction "1_1") (pintype "passive"))
    )
    (net (code "97") (name "unconnected-(OUTPUT-Pad7)") (class "Default")
      (node (ref "OUTPUT") (pin "7") (pinfunction "7_7") (pintype "passive"))
    )
    (net (code "98") (name "unconnected-(PWR-IN-Pad2)") (class "Default")
      (node (ref "PWR-IN") (pin "2") (pinfunction "2_2") (pintype "passive"))
    )
    (net (code "99") (name "unconnected-(PWR-IN-Pad3)") (class "Default")
      (node (ref "PWR-IN") (pin "3") (pinfunction "3_3") (pintype "passive"))
    )
    (net (code "100") (name "unconnected-(PWR-IN-Pad4)") (class "Default")
      (node (ref "PWR-IN") (pin "4") (pinfunction "4_4") (pintype "passive"))
    )
    (net (code "101") (name "unconnected-(PWR-IN-Pad5)") (class "Default")
      (node (ref "PWR-IN") (pin "5") (pinfunction "5_5") (pintype "passive"))
    )
    (net (code "102") (name "unconnected-(PWR-IN-Pad6)") (class "Default")
      (node (ref "PWR-IN") (pin "6") (pinfunction "6_6") (pintype "passive"))
    )
  )
)
